# P_12_SOM_Interface.net
KiCad netlist of a schematic drawn in Altium Designer
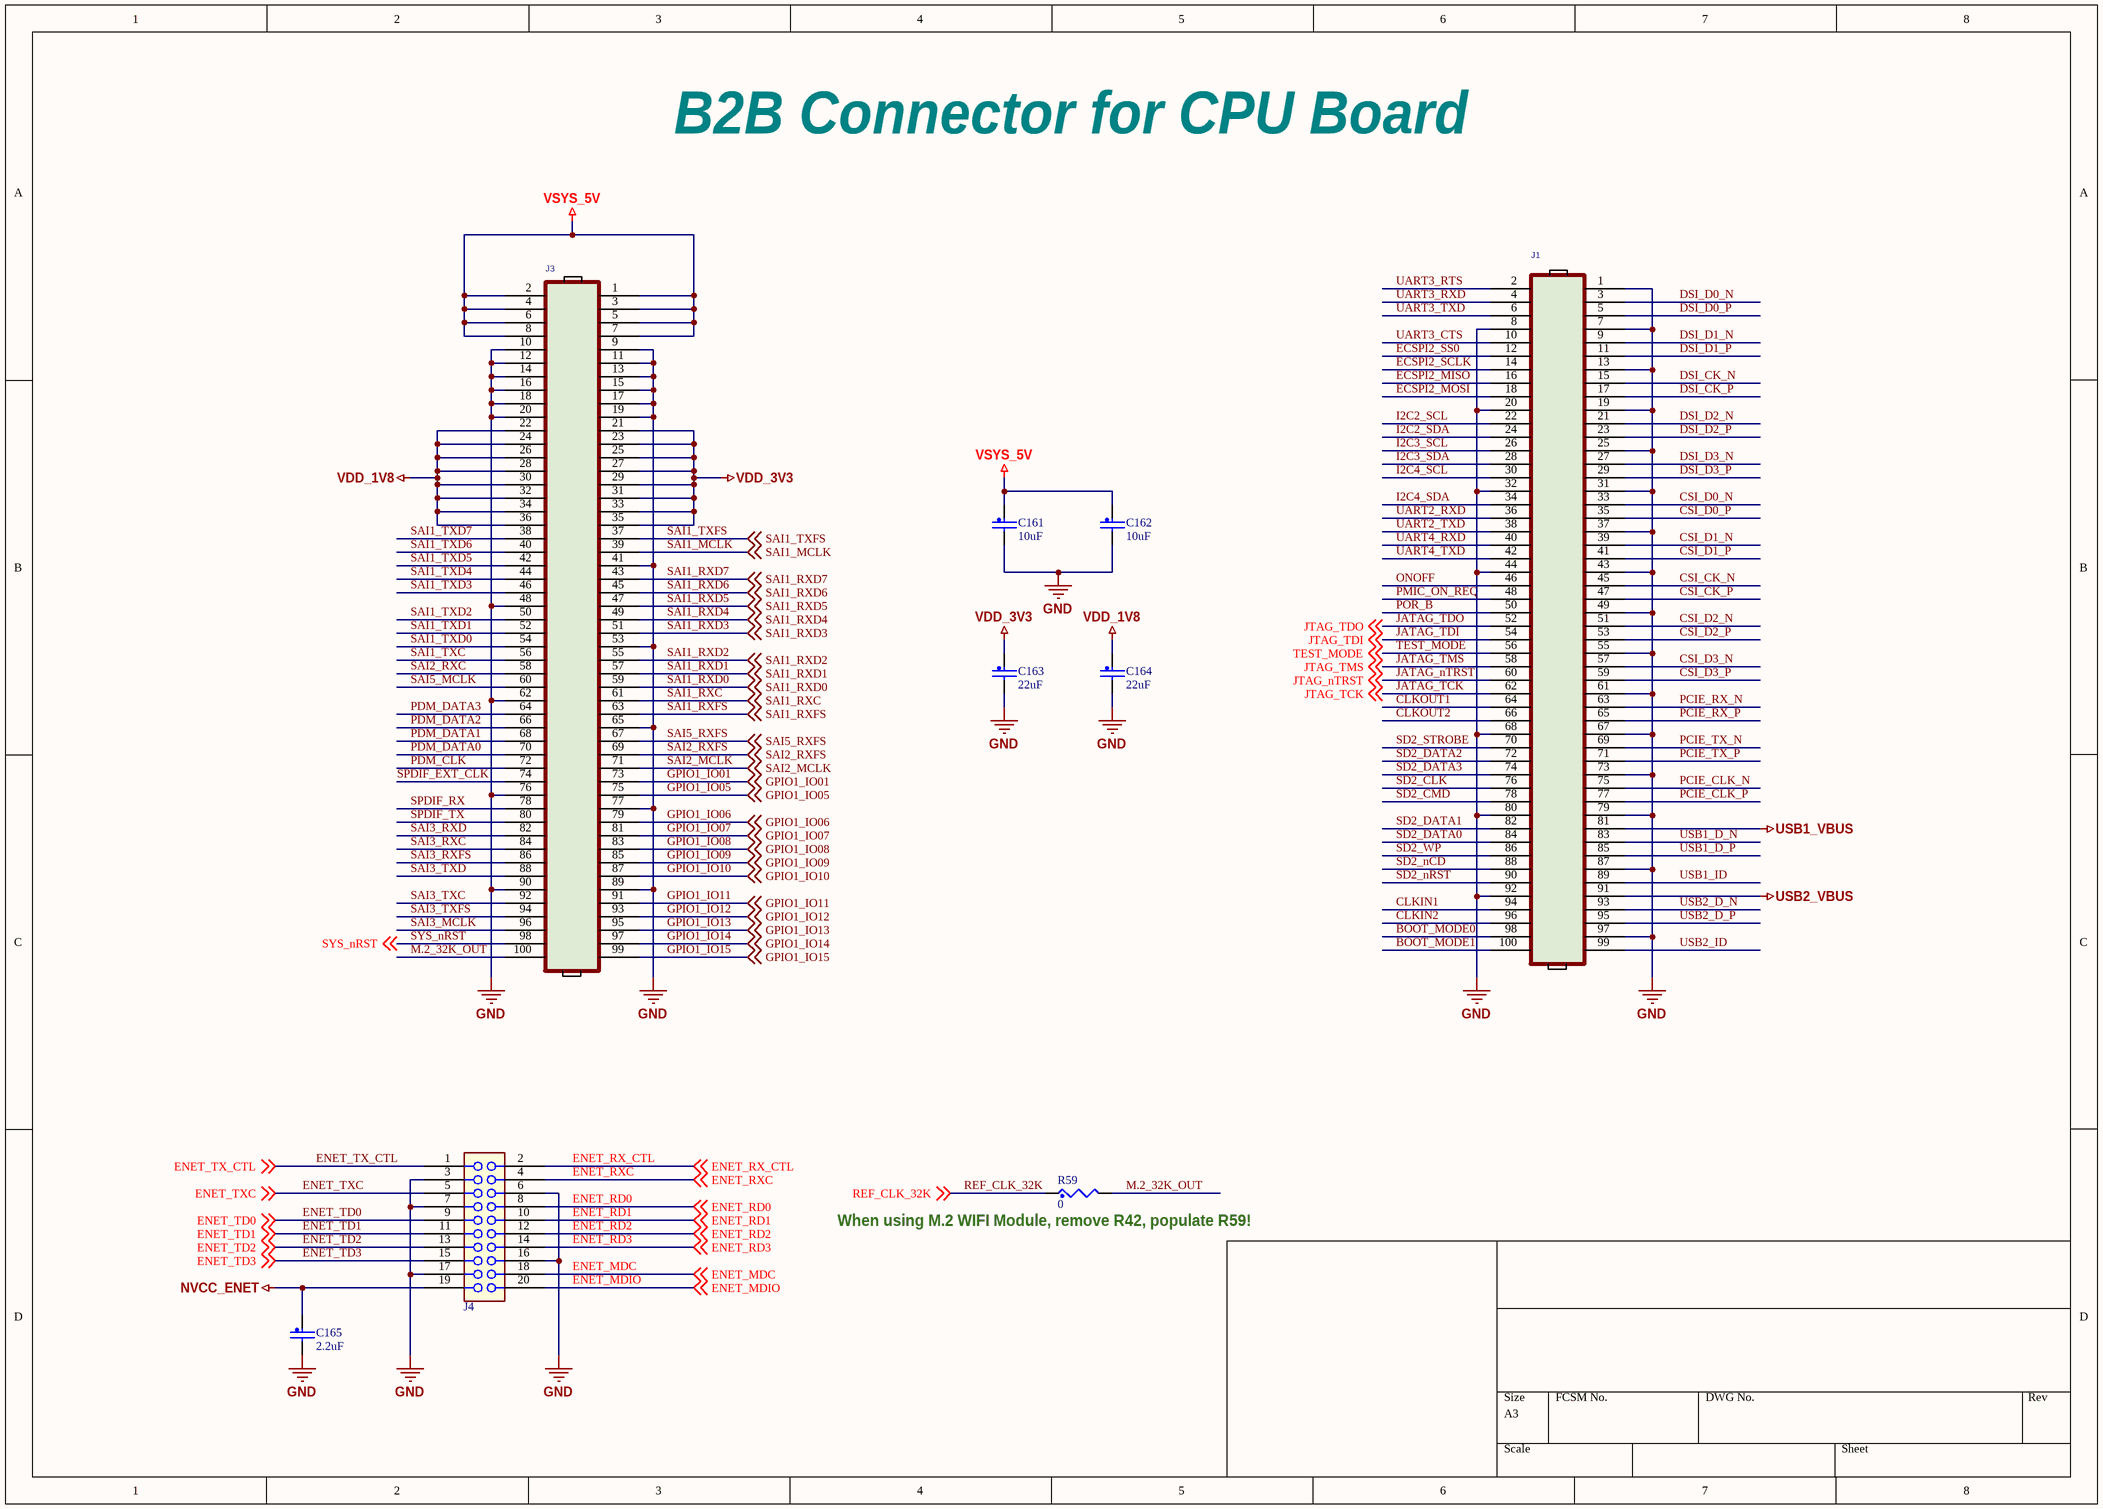
[diagram p0: P[12]SOM_Interface.SchDoc]

(export (version "E")
  (design (tool "Eeschema 10.0.6"))
  (components
    (comp (ref "C161") (value "10uF") (footprint "0603_CC") (libsource (lib "AA_iMX8_M_") (part "CAP_NP")))
    (comp (ref "C162") (value "10uF") (footprint "0603_CC") (libsource (lib "AA_iMX8_M_") (part "CAP_NP")))
    (comp (ref "C163") (value "22uF") (footprint "0603_CC") (libsource (lib "AA_iMX8_M_") (part "CAP_NP")))
    (comp (ref "C164") (value "22uF") (footprint "0603_CC") (libsource (lib "AA_iMX8_M_") (part "CAP_NP")))
    (comp (ref "C165")
      (value "2.2uF")
      (footprint "0402_CC - C")
      (libsource (lib "AA_iMX8_M_") (part "CAP_NP"))
    )
    (comp (ref "J1")
      (value "CON 2X50 PLUG SHRD SMT 0.4MM SP 51H AU")
      (footprint "CON100_0P4_21P7X2P05_SM")
      (libsource (lib "AA_iMX8_M_") (part "HDR_2X50_M"))
    )
    (comp (ref "J3")
      (value "CON 2X50 PLUG SHRD SMT 0.4MM SP 51H AU")
      (footprint "CON100_0P4_22P8X3P1_SM")
      (libsource (lib "AA_iMX8_M_") (part "HDR_2X50_M"))
    )
    (comp (ref "J4")
      (value "CONN_HDR_10X2_CON20_0P4_6P8X3P1")
      (footprint "CON20_0P4_6P8X3P1_SM")
      (description "CONN_HDR_10X2_CON20_0P4_6P8X3P1\\By Arman Arvand")
      (libsource (lib "AA_iMX8_M_") (part "CONN_HDR_10X2"))
    )
    (comp (ref "R59") (value "0") (footprint "0402_CC") (libsource (lib "AA_iMX8_M_") (part "RES")))
  )
  (nets
    (net (code "1") (name "/BOOT_MODE0") (class "Default")
      (node (ref "J1") (pin "98") (pinfunction "98_98") (pintype "passive"))
    )
    (net (code "2") (name "/BOOT_MODE1") (class "Default")
      (node (ref "J1") (pin "100") (pinfunction "100_100") (pintype "passive"))
    )
    (net (code "3") (name "/CLKIN1") (class "Default")
      (node (ref "J1") (pin "94") (pinfunction "94_94") (pintype "passive"))
    )
    (net (code "4") (name "/CLKIN2") (class "Default")
      (node (ref "J1") (pin "96") (pinfunction "96_96") (pintype "passive"))
    )
    (net (code "5") (name "/CLKOUT1") (class "Default")
      (node (ref "J1") (pin "64") (pinfunction "64_64") (pintype "passive"))
    )
    (net (code "6") (name "/CLKOUT2") (class "Default")
      (node (ref "J1") (pin "66") (pinfunction "66_66") (pintype "passive"))
    )
    (net (code "7") (name "/CSI_CK_N") (class "Default")
      (node (ref "J1") (pin "45") (pinfunction "45_45") (pintype "passive"))
    )
    (net (code "8") (name "/CSI_CK_P") (class "Default")
      (node (ref "J1") (pin "47") (pinfunction "47_47") (pintype "passive"))
    )
    (net (code "9") (name "/CSI_D0_N") (class "Default")
      (node (ref "J1") (pin "33") (pinfunction "33_33") (pintype "passive"))
    )
    (net (code "10") (name "/CSI_D0_P") (class "Default")
      (node (ref "J1") (pin "35") (pinfunction "35_35") (pintype "passive"))
    )
    (net (code "11") (name "/CSI_D1_N") (class "Default")
      (node (ref "J1") (pin "39") (pinfunction "39_39") (pintype "passive"))
    )
    (net (code "12") (name "/CSI_D1_P") (class "Default")
      (node (ref "J1") (pin "41") (pinfunction "41_41") (pintype "passive"))
    )
    (net (code "13") (name "/CSI_D2_N") (class "Default")
      (node (ref "J1") (pin "51") (pinfunction "51_51") (pintype "passive"))
    )
    (net (code "14") (name "/CSI_D2_P") (class "Default")
      (node (ref "J1") (pin "53") (pinfunction "53_53") (pintype "passive"))
    )
    (net (code "15") (name "/CSI_D3_N") (class "Default")
      (node (ref "J1") (pin "57") (pinfunction "57_57") (pintype "passive"))
    )
    (net (code "16") (name "/CSI_D3_P") (class "Default")
      (node (ref "J1") (pin "59") (pinfunction "59_59") (pintype "passive"))
    )
    (net (code "17") (name "/DSI_CK_N") (class "Default")
      (node (ref "J1") (pin "15") (pinfunction "15_15") (pintype "passive"))
    )
    (net (code "18") (name "/DSI_CK_P") (class "Default")
      (node (ref "J1") (pin "17") (pinfunction "17_17") (pintype "passive"))
    )
    (net (code "19") (name "/DSI_D0_N") (class "Default")
      (node (ref "J1") (pin "3") (pinfunction "3_3") (pintype "passive"))
    )
    (net (code "20") (name "/DSI_D0_P") (class "Default")
      (node (ref "J1") (pin "5") (pinfunction "5_5") (pintype "passive"))
    )
    (net (code "21") (name "/DSI_D1_N") (class "Default")
      (node (ref "J1") (pin "9") (pinfunction "9_9") (pintype "passive"))
    )
    (net (code "22") (name "/DSI_D1_P") (class "Default")
      (node (ref "J1") (pin "11") (pinfunction "11_11") (pintype "passive"))
    )
    (net (code "23") (name "/DSI_D2_N") (class "Default")
      (node (ref "J1") (pin "21") (pinfunction "21_21") (pintype "passive"))
    )
    (net (code "24") (name "/DSI_D2_P") (class "Default")
      (node (ref "J1") (pin "23") (pinfunction "23_23") (pintype "passive"))
    )
    (net (code "25") (name "/DSI_D3_N") (class "Default")
      (node (ref "J1") (pin "27") (pinfunction "27_27") (pintype "passive"))
    )
    (net (code "26") (name "/DSI_D3_P") (class "Default")
      (node (ref "J1") (pin "29") (pinfunction "29_29") (pintype "passive"))
    )
    (net (code "27") (name "/ECSPI2_MISO") (class "Default")
      (node (ref "J1") (pin "16") (pinfunction "16_16") (pintype "passive"))
    )
    (net (code "28") (name "/ECSPI2_MOSI") (class "Default")
      (node (ref "J1") (pin "18") (pinfunction "18_18") (pintype "passive"))
    )
    (net (code "29") (name "/ECSPI2_SCLK") (class "Default")
      (node (ref "J1") (pin "14") (pinfunction "14_14") (pintype "passive"))
    )
    (net (code "30") (name "/ECSPI2_SS0") (class "Default")
      (node (ref "J1") (pin "12") (pinfunction "12_12") (pintype "passive"))
    )
    (net (code "31") (name "/I2C2_SCL") (class "Default")
      (node (ref "J1") (pin "22") (pinfunction "22_22") (pintype "passive"))
    )
    (net (code "32") (name "/I2C2_SDA") (class "Default")
      (node (ref "J1") (pin "24") (pinfunction "24_24") (pintype "passive"))
    )
    (net (code "33") (name "/I2C3_SCL") (class "Default")
      (node (ref "J1") (pin "26") (pinfunction "26_26") (pintype "passive"))
    )
    (net (code "34") (name "/I2C3_SDA") (class "Default")
      (node (ref "J1") (pin "28") (pinfunction "28_28") (pintype "passive"))
    )
    (net (code "35") (name "/I2C4_SCL") (class "Default")
      (node (ref "J1") (pin "30") (pinfunction "30_30") (pintype "passive"))
    )
    (net (code "36") (name "/I2C4_SDA") (class "Default")
      (node (ref "J1") (pin "34") (pinfunction "34_34") (pintype "passive"))
    )
    (net (code "37") (name "/M.2_32K_OUT") (class "Default")
      (node (ref "J3") (pin "100") (pinfunction "100_100") (pintype "passive"))
      (node (ref "R59") (pin "2") (pinfunction "2_2") (pintype "passive"))
    )
    (net (code "38") (name "/ONOFF") (class "Default")
      (node (ref "J1") (pin "46") (pinfunction "46_46") (pintype "passive"))
    )
    (net (code "39") (name "/PCIE_CLK_N") (class "Default")
      (node (ref "J1") (pin "75") (pinfunction "75_75") (pintype "passive"))
    )
    (net (code "40") (name "/PCIE_CLK_P") (class "Default")
      (node (ref "J1") (pin "77") (pinfunction "77_77") (pintype "passive"))
    )
    (net (code "41") (name "/PCIE_RX_N") (class "Default")
      (node (ref "J1") (pin "63") (pinfunction "63_63") (pintype "passive"))
    )
    (net (code "42") (name "/PCIE_RX_P") (class "Default")
      (node (ref "J1") (pin "65") (pinfunction "65_65") (pintype "passive"))
    )
    (net (code "43") (name "/PCIE_TX_N") (class "Default")
      (node (ref "J1") (pin "69") (pinfunction "69_69") (pintype "passive"))
    )
    (net (code "44") (name "/PCIE_TX_P") (class "Default")
      (node (ref "J1") (pin "71") (pinfunction "71_71") (pintype "passive"))
    )
    (net (code "45") (name "/PDM_CLK") (class "Default")
      (node (ref "J3") (pin "72") (pinfunction "72_72") (pintype "passive"))
    )
    (net (code "46") (name "/PDM_DATA0") (class "Default")
      (node (ref "J3") (pin "70") (pinfunction "70_70") (pintype "passive"))
    )
    (net (code "47") (name "/PDM_DATA1") (class "Default")
      (node (ref "J3") (pin "68") (pinfunction "68_68") (pintype "passive"))
    )
    (net (code "48") (name "/PDM_DATA2") (class "Default")
      (node (ref "J3") (pin "66") (pinfunction "66_66") (pintype "passive"))
    )
    (net (code "49") (name "/PDM_DATA3") (class "Default")
      (node (ref "J3") (pin "64") (pinfunction "64_64") (pintype "passive"))
    )
    (net (code "50") (name "/PMIC_ON_REQ") (class "Default")
      (node (ref "J1") (pin "48") (pinfunction "48_48") (pintype "passive"))
    )
    (net (code "51") (name "/POR_B") (class "Default")
      (node (ref "J1") (pin "50") (pinfunction "50_50") (pintype "passive"))
    )
    (net (code "52") (name "/SAI1_TXC") (class "Default")
      (node (ref "J3") (pin "56") (pinfunction "56_56") (pintype "passive"))
    )
    (net (code "53") (name "/SAI1_TXD0") (class "Default")
      (node (ref "J3") (pin "54") (pinfunction "54_54") (pintype "passive"))
    )
    (net (code "54") (name "/SAI1_TXD1") (class "Default")
      (node (ref "J3") (pin "52") (pinfunction "52_52") (pintype "passive"))
    )
    (net (code "55") (name "/SAI1_TXD2") (class "Default")
      (node (ref "J3") (pin "50") (pinfunction "50_50") (pintype "passive"))
    )
    (net (code "56") (name "/SAI1_TXD3") (class "Default")
      (node (ref "J3") (pin "46") (pinfunction "46_46") (pintype "passive"))
    )
    (net (code "57") (name "/SAI1_TXD4") (class "Default")
      (node (ref "J3") (pin "44") (pinfunction "44_44") (pintype "passive"))
    )
    (net (code "58") (name "/SAI1_TXD5") (class "Default")
      (node (ref "J3") (pin "42") (pinfunction "42_42") (pintype "passive"))
    )
    (net (code "59") (name "/SAI1_TXD6") (class "Default")
      (node (ref "J3") (pin "40") (pinfunction "40_40") (pintype "passive"))
    )
    (net (code "60") (name "/SAI1_TXD7") (class "Default")
      (node (ref "J3") (pin "38") (pinfunction "38_38") (pintype "passive"))
    )
    (net (code "61") (name "/SAI2_RXC") (class "Default")
      (node (ref "J3") (pin "58") (pinfunction "58_58") (pintype "passive"))
    )
    (net (code "62") (name "/SAI3_MCLK") (class "Default")
      (node (ref "J3") (pin "96") (pinfunction "96_96") (pintype "passive"))
    )
    (net (code "63") (name "/SAI3_RXC") (class "Default")
      (node (ref "J3") (pin "84") (pinfunction "84_84") (pintype "passive"))
    )
    (net (code "64") (name "/SAI3_RXD") (class "Default")
      (node (ref "J3") (pin "82") (pinfunction "82_82") (pintype "passive"))
    )
    (net (code "65") (name "/SAI3_RXFS") (class "Default")
      (node (ref "J3") (pin "86") (pinfunction "86_86") (pintype "passive"))
    )
    (net (code "66") (name "/SAI3_TXC") (class "Default")
      (node (ref "J3") (pin "92") (pinfunction "92_92") (pintype "passive"))
    )
    (net (code "67") (name "/SAI3_TXD") (class "Default")
      (node (ref "J3") (pin "88") (pinfunction "88_88") (pintype "passive"))
    )
    (net (code "68") (name "/SAI3_TXFS") (class "Default")
      (node (ref "J3") (pin "94") (pinfunction "94_94") (pintype "passive"))
    )
    (net (code "69") (name "/SAI5_MCLK") (class "Default")
      (node (ref "J3") (pin "60") (pinfunction "60_60") (pintype "passive"))
    )
    (net (code "70") (name "/SD2_CLK") (class "Default")
      (node (ref "J1") (pin "76") (pinfunction "76_76") (pintype "passive"))
    )
    (net (code "71") (name "/SD2_CMD") (class "Default")
      (node (ref "J1") (pin "78") (pinfunction "78_78") (pintype "passive"))
    )
    (net (code "72") (name "/SD2_DATA0") (class "Default")
      (node (ref "J1") (pin "84") (pinfunction "84_84") (pintype "passive"))
    )
    (net (code "73") (name "/SD2_DATA1") (class "Default")
      (node (ref "J1") (pin "82") (pinfunction "82_82") (pintype "passive"))
    )
    (net (code "74") (name "/SD2_DATA2") (class "Default")
      (node (ref "J1") (pin "72") (pinfunction "72_72") (pintype "passive"))
    )
    (net (code "75") (name "/SD2_DATA3") (class "Default")
      (node (ref "J1") (pin "74") (pinfunction "74_74") (pintype "passive"))
    )
    (net (code "76") (name "/SD2_STROBE") (class "Default")
      (node (ref "J1") (pin "70") (pinfunction "70_70") (pintype "passive"))
    )
    (net (code "77") (name "/SD2_WP") (class "Default")
      (node (ref "J1") (pin "86") (pinfunction "86_86") (pintype "passive"))
    )
    (net (code "78") (name "/SD2_nCD") (class "Default")
      (node (ref "J1") (pin "88") (pinfunction "88_88") (pintype "passive"))
    )
    (net (code "79") (name "/SD2_nRST") (class "Default")
      (node (ref "J1") (pin "90") (pinfunction "90_90") (pintype "passive"))
    )
    (net (code "80") (name "/SPDIF_EXT_CLK") (class "Default")
      (node (ref "J3") (pin "74") (pinfunction "74_74") (pintype "passive"))
    )
    (net (code "81") (name "/SPDIF_RX") (class "Default")
      (node (ref "J3") (pin "78") (pinfunction "78_78") (pintype "passive"))
    )
    (net (code "82") (name "/SPDIF_TX") (class "Default")
      (node (ref "J3") (pin "80") (pinfunction "80_80") (pintype "passive"))
    )
    (net (code "83") (name "/UART2_RXD") (class "Default")
      (node (ref "J1") (pin "36") (pinfunction "36_36") (pintype "passive"))
    )
    (net (code "84") (name "/UART2_TXD") (class "Default")
      (node (ref "J1") (pin "38") (pinfunction "38_38") (pintype "passive"))
    )
    (net (code "85") (name "/UART3_CTS") (class "Default")
      (node (ref "J1") (pin "10") (pinfunction "10_10") (pintype "passive"))
    )
    (net (code "86") (name "/UART3_RTS") (class "Default")
      (node (ref "J1") (pin "2") (pinfunction "2_2") (pintype "passive"))
    )
    (net (code "87") (name "/UART3_RXD") (class "Default")
      (node (ref "J1") (pin "4") (pinfunction "4_4") (pintype "passive"))
    )
    (net (code "88") (name "/UART3_TXD") (class "Default")
      (node (ref "J1") (pin "6") (pinfunction "6_6") (pintype "passive"))
    )
    (net (code "89") (name "/UART4_RXD") (class "Default")
      (node (ref "J1") (pin "40") (pinfunction "40_40") (pintype "passive"))
    )
    (net (code "90") (name "/UART4_TXD") (class "Default")
      (node (ref "J1") (pin "42") (pinfunction "42_42") (pintype "passive"))
    )
    (net (code "91") (name "/USB1_D_N") (class "Default")
      (node (ref "J1") (pin "83") (pinfunction "83_83") (pintype "passive"))
    )
    (net (code "92") (name "/USB1_D_P") (class "Default")
      (node (ref "J1") (pin "85") (pinfunction "85_85") (pintype "passive"))
    )
    (net (code "93") (name "/USB1_ID") (class "Default")
      (node (ref "J1") (pin "89") (pinfunction "89_89") (pintype "passive"))
    )
    (net (code "94") (name "/USB2_D_N") (class "Default")
      (node (ref "J1") (pin "93") (pinfunction "93_93") (pintype "passive"))
    )
    (net (code "95") (name "/USB2_D_P") (class "Default")
      (node (ref "J1") (pin "95") (pinfunction "95_95") (pintype "passive"))
    )
    (net (code "96") (name "/USB2_ID") (class "Default")
      (node (ref "J1") (pin "99") (pinfunction "99_99") (pintype "passive"))
    )
    (net (code "97") (name "ENET_MDC") (class "Default")
      (node (ref "J4") (pin "18") (pinfunction "18_18") (pintype "passive"))
    )
    (net (code "98") (name "ENET_MDIO") (class "Default")
      (node (ref "J4") (pin "20") (pinfunction "20_20") (pintype "passive"))
    )
    (net (code "99") (name "ENET_RD0") (class "Default")
      (node (ref "J4") (pin "8") (pinfunction "8_8") (pintype "passive"))
    )
    (net (code "100") (name "ENET_RD1") (class "Default")
      (node (ref "J4") (pin "10") (pinfunction "10_10") (pintype "passive"))
    )
    (net (code "101") (name "ENET_RD2") (class "Default")
      (node (ref "J4") (pin "12") (pinfunction "12_12") (pintype "passive"))
    )
    (net (code "102") (name "ENET_RD3") (class "Default")
      (node (ref "J4") (pin "14") (pinfunction "14_14") (pintype "passive"))
    )
    (net (code "103") (name "ENET_RXC") (class "Default")
      (node (ref "J4") (pin "4") (pinfunction "4_4") (pintype "passive"))
    )
    (net (code "104") (name "ENET_RX_CTL") (class "Default")
      (node (ref "J4") (pin "2") (pinfunction "2_2") (pintype "passive"))
    )
    (net (code "105") (name "ENET_TD0") (class "Default")
      (node (ref "J4") (pin "9") (pinfunction "9_9") (pintype "passive"))
    )
    (net (code "106") (name "ENET_TD1") (class "Default")
      (node (ref "J4") (pin "11") (pinfunction "11_11") (pintype "passive"))
    )
    (net (code "107") (name "ENET_TD2") (class "Default")
      (node (ref "J4") (pin "13") (pinfunction "13_13") (pintype "passive"))
    )
    (net (code "108") (name "ENET_TD3") (class "Default")
      (node (ref "J4") (pin "15") (pinfunction "15_15") (pintype "passive"))
    )
    (net (code "109") (name "ENET_TXC") (class "Default")
      (node (ref "J4") (pin "5") (pinfunction "5_5") (pintype "passive"))
    )
    (net (code "110") (name "ENET_TX_CTL") (class "Default")
      (node (ref "J4") (pin "1") (pinfunction "1_1") (pintype "passive"))
    )
    (net (code "111") (name "GND") (class "Default")
      (node (ref "C161") (pin "2") (pinfunction "2_2") (pintype "passive"))
      (node (ref "C162") (pin "2") (pinfunction "2_2") (pintype "passive"))
      (node (ref "C163") (pin "2") (pinfunction "2_2") (pintype "passive"))
      (node (ref "C164") (pin "2") (pinfunction "2_2") (pintype "passive"))
      (node (ref "C165") (pin "2") (pinfunction "2_2") (pintype "passive"))
      (node (ref "J1") (pin "1") (pinfunction "1_1") (pintype "passive"))
      (node (ref "J1") (pin "13") (pinfunction "13_13") (pintype "passive"))
      (node (ref "J1") (pin "19") (pinfunction "19_19") (pintype "passive"))
      (node (ref "J1") (pin "20") (pinfunction "20_20") (pintype "passive"))
      (node (ref "J1") (pin "25") (pinfunction "25_25") (pintype "passive"))
      (node (ref "J1") (pin "31") (pinfunction "31_31") (pintype "passive"))
      (node (ref "J1") (pin "32") (pinfunction "32_32") (pintype "passive"))
      (node (ref "J1") (pin "37") (pinfunction "37_37") (pintype "passive"))
      (node (ref "J1") (pin "43") (pinfunction "43_43") (pintype "passive"))
      (node (ref "J1") (pin "44") (pinfunction "44_44") (pintype "passive"))
      (node (ref "J1") (pin "49") (pinfunction "49_49") (pintype "passive"))
      (node (ref "J1") (pin "55") (pinfunction "55_55") (pintype "passive"))
      (node (ref "J1") (pin "61") (pinfunction "61_61") (pintype "passive"))
      (node (ref "J1") (pin "67") (pinfunction "67_67") (pintype "passive"))
      (node (ref "J1") (pin "68") (pinfunction "68_68") (pintype "passive"))
      (node (ref "J1") (pin "7") (pinfunction "7_7") (pintype "passive"))
      (node (ref "J1") (pin "73") (pinfunction "73_73") (pintype "passive"))
      (node (ref "J1") (pin "79") (pinfunction "79_79") (pintype "passive"))
      (node (ref "J1") (pin "8") (pinfunction "8_8") (pintype "passive"))
      (node (ref "J1") (pin "80") (pinfunction "80_80") (pintype "passive"))
      (node (ref "J1") (pin "87") (pinfunction "87_87") (pintype "passive"))
      (node (ref "J1") (pin "92") (pinfunction "92_92") (pintype "passive"))
      (node (ref "J1") (pin "97") (pinfunction "97_97") (pintype "passive"))
      (node (ref "J3") (pin "10") (pinfunction "10_10") (pintype "passive"))
      (node (ref "J3") (pin "11") (pinfunction "11_11") (pintype "passive"))
      (node (ref "J3") (pin "12") (pinfunction "12_12") (pintype "passive"))
      (node (ref "J3") (pin "13") (pinfunction "13_13") (pintype "passive"))
      (node (ref "J3") (pin "14") (pinfunction "14_14") (pintype "passive"))
      (node (ref "J3") (pin "15") (pinfunction "15_15") (pintype "passive"))
      (node (ref "J3") (pin "16") (pinfunction "16_16") (pintype "passive"))
      (node (ref "J3") (pin "17") (pinfunction "17_17") (pintype "passive"))
      (node (ref "J3") (pin "18") (pinfunction "18_18") (pintype "passive"))
      (node (ref "J3") (pin "19") (pinfunction "19_19") (pintype "passive"))
      (node (ref "J3") (pin "20") (pinfunction "20_20") (pintype "passive"))
      (node (ref "J3") (pin "41") (pinfunction "41_41") (pintype "passive"))
      (node (ref "J3") (pin "48") (pinfunction "48_48") (pintype "passive"))
      (node (ref "J3") (pin "53") (pinfunction "53_53") (pintype "passive"))
      (node (ref "J3") (pin "62") (pinfunction "62_62") (pintype "passive"))
      (node (ref "J3") (pin "65") (pinfunction "65_65") (pintype "passive"))
      (node (ref "J3") (pin "76") (pinfunction "76_76") (pintype "passive"))
      (node (ref "J3") (pin "77") (pinfunction "77_77") (pintype "passive"))
      (node (ref "J3") (pin "89") (pinfunction "89_89") (pintype "passive"))
      (node (ref "J3") (pin "9") (pinfunction "9_9") (pintype "passive"))
      (node (ref "J3") (pin "90") (pinfunction "90_90") (pintype "passive"))
      (node (ref "J4") (pin "16") (pinfunction "16_16") (pintype "passive"))
      (node (ref "J4") (pin "17") (pinfunction "17_17") (pintype "passive"))
      (node (ref "J4") (pin "3") (pinfunction "3_3") (pintype "passive"))
      (node (ref "J4") (pin "6") (pinfunction "6_6") (pintype "passive"))
      (node (ref "J4") (pin "7") (pinfunction "7_7") (pintype "passive"))
    )
    (net (code "112") (name "GPIO1_IO01") (class "Default")
      (node (ref "J3") (pin "73") (pinfunction "73_73") (pintype "passive"))
    )
    (net (code "113") (name "GPIO1_IO05") (class "Default")
      (node (ref "J3") (pin "75") (pinfunction "75_75") (pintype "passive"))
    )
    (net (code "114") (name "GPIO1_IO06") (class "Default")
      (node (ref "J3") (pin "79") (pinfunction "79_79") (pintype "passive"))
    )
    (net (code "115") (name "GPIO1_IO07") (class "Default")
      (node (ref "J3") (pin "81") (pinfunction "81_81") (pintype "passive"))
    )
    (net (code "116") (name "GPIO1_IO08") (class "Default")
      (node (ref "J3") (pin "83") (pinfunction "83_83") (pintype "passive"))
    )
    (net (code "117") (name "GPIO1_IO09") (class "Default")
      (node (ref "J3") (pin "85") (pinfunction "85_85") (pintype "passive"))
    )
    (net (code "118") (name "GPIO1_IO10") (class "Default")
      (node (ref "J3") (pin "87") (pinfunction "87_87") (pintype "passive"))
    )
    (net (code "119") (name "GPIO1_IO11") (class "Default")
      (node (ref "J3") (pin "91") (pinfunction "91_91") (pintype "passive"))
    )
    (net (code "120") (name "GPIO1_IO12") (class "Default")
      (node (ref "J3") (pin "93") (pinfunction "93_93") (pintype "passive"))
    )
    (net (code "121") (name "GPIO1_IO13") (class "Default")
      (node (ref "J3") (pin "95") (pinfunction "95_95") (pintype "passive"))
    )
    (net (code "122") (name "GPIO1_IO14") (class "Default")
      (node (ref "J3") (pin "97") (pinfunction "97_97") (pintype "passive"))
    )
    (net (code "123") (name "GPIO1_IO15") (class "Default")
      (node (ref "J3") (pin "99") (pinfunction "99_99") (pintype "passive"))
    )
    (net (code "124") (name "JTAG_TCK") (class "Default")
      (node (ref "J1") (pin "62") (pinfunction "62_62") (pintype "passive"))
    )
    (net (code "125") (name "JTAG_TDI") (class "Default")
      (node (ref "J1") (pin "54") (pinfunction "54_54") (pintype "passive"))
    )
    (net (code "126") (name "JTAG_TDO") (class "Default")
      (node (ref "J1") (pin "52") (pinfunction "52_52") (pintype "passive"))
    )
    (net (code "127") (name "JTAG_TMS") (class "Default")
      (node (ref "J1") (pin "58") (pinfunction "58_58") (pintype "passive"))
    )
    (net (code "128") (name "JTAG_nTRST") (class "Default")
      (node (ref "J1") (pin "60") (pinfunction "60_60") (pintype "passive"))
    )
    (net (code "129") (name "NVCC_ENET") (class "Default")
      (node (ref "C165") (pin "1") (pinfunction "1_1") (pintype "passive"))
      (node (ref "J4") (pin "19") (pinfunction "19_19") (pintype "passive"))
    )
    (net (code "130") (name "REF_CLK_32K") (class "Default")
      (node (ref "R59") (pin "1") (pinfunction "1_1") (pintype "passive"))
    )
    (net (code "131") (name "SAI1_MCLK") (class "Default")
      (node (ref "J3") (pin "39") (pinfunction "39_39") (pintype "passive"))
    )
    (net (code "132") (name "SAI1_RXC") (class "Default")
      (node (ref "J3") (pin "61") (pinfunction "61_61") (pintype "passive"))
    )
    (net (code "133") (name "SAI1_RXD0") (class "Default")
      (node (ref "J3") (pin "59") (pinfunction "59_59") (pintype "passive"))
    )
    (net (code "134") (name "SAI1_RXD1") (class "Default")
      (node (ref "J3") (pin "57") (pinfunction "57_57") (pintype "passive"))
    )
    (net (code "135") (name "SAI1_RXD2") (class "Default")
      (node (ref "J3") (pin "55") (pinfunction "55_55") (pintype "passive"))
    )
    (net (code "136") (name "SAI1_RXD3") (class "Default")
      (node (ref "J3") (pin "51") (pinfunction "51_51") (pintype "passive"))
    )
    (net (code "137") (name "SAI1_RXD4") (class "Default")
      (node (ref "J3") (pin "49") (pinfunction "49_49") (pintype "passive"))
    )
    (net (code "138") (name "SAI1_RXD5") (class "Default")
      (node (ref "J3") (pin "47") (pinfunction "47_47") (pintype "passive"))
    )
    (net (code "139") (name "SAI1_RXD6") (class "Default")
      (node (ref "J3") (pin "45") (pinfunction "45_45") (pintype "passive"))
    )
    (net (code "140") (name "SAI1_RXD7") (class "Default")
      (node (ref "J3") (pin "43") (pinfunction "43_43") (pintype "passive"))
    )
    (net (code "141") (name "SAI1_RXFS") (class "Default")
      (node (ref "J3") (pin "63") (pinfunction "63_63") (pintype "passive"))
    )
    (net (code "142") (name "SAI1_TXFS") (class "Default")
      (node (ref "J3") (pin "37") (pinfunction "37_37") (pintype "passive"))
    )
    (net (code "143") (name "SAI2_MCLK") (class "Default")
      (node (ref "J3") (pin "71") (pinfunction "71_71") (pintype "passive"))
    )
    (net (code "144") (name "SAI2_RXFS") (class "Default")
      (node (ref "J3") (pin "69") (pinfunction "69_69") (pintype "passive"))
    )
    (net (code "145") (name "SAI5_RXFS") (class "Default")
      (node (ref "J3") (pin "67") (pinfunction "67_67") (pintype "passive"))
    )
    (net (code "146") (name "SYS_nRST") (class "Default")
      (node (ref "J3") (pin "98") (pinfunction "98_98") (pintype "passive"))
    )
    (net (code "147") (name "TEST_MODE") (class "Default")
      (node (ref "J1") (pin "56") (pinfunction "56_56") (pintype "passive"))
    )
    (net (code "148") (name "USB1_VBUS") (class "Default")
      (node (ref "J1") (pin "81") (pinfunction "81_81") (pintype "passive"))
    )
    (net (code "149") (name "USB2_VBUS") (class "Default")
      (node (ref "J1") (pin "91") (pinfunction "91_91") (pintype "passive"))
    )
    (net (code "150") (name "VDD_1V8") (class "Default")
      (node (ref "C164") (pin "1") (pinfunction "1_1") (pintype "passive"))
      (node (ref "J3") (pin "22") (pinfunction "22_22") (pintype "passive"))
      (node (ref "J3") (pin "24") (pinfunction "24_24") (pintype "passive"))
      (node (ref "J3") (pin "26") (pinfunction "26_26") (pintype "passive"))
      (node (ref "J3") (pin "28") (pinfunction "28_28") (pintype "passive"))
      (node (ref "J3") (pin "30") (pinfunction "30_30") (pintype "passive"))
      (node (ref "J3") (pin "32") (pinfunction "32_32") (pintype "passive"))
      (node (ref "J3") (pin "34") (pinfunction "34_34") (pintype "passive"))
      (node (ref "J3") (pin "36") (pinfunction "36_36") (pintype "passive"))
    )
    (net (code "151") (name "VDD_3V3") (class "Default")
      (node (ref "C163") (pin "1") (pinfunction "1_1") (pintype "passive"))
      (node (ref "J3") (pin "21") (pinfunction "21_21") (pintype "passive"))
      (node (ref "J3") (pin "23") (pinfunction "23_23") (pintype "passive"))
      (node (ref "J3") (pin "25") (pinfunction "25_25") (pintype "passive"))
      (node (ref "J3") (pin "27") (pinfunction "27_27") (pintype "passive"))
      (node (ref "J3") (pin "29") (pinfunction "29_29") (pintype "passive"))
      (node (ref "J3") (pin "31") (pinfunction "31_31") (pintype "passive"))
      (node (ref "J3") (pin "33") (pinfunction "33_33") (pintype "passive"))
      (node (ref "J3") (pin "35") (pinfunction "35_35") (pintype "passive"))
    )
    (net (code "152") (name "VSYS_5V") (class "Default")
      (node (ref "C161") (pin "1") (pinfunction "1_1") (pintype "passive"))
      (node (ref "C162") (pin "1") (pinfunction "1_1") (pintype "passive"))
      (node (ref "J3") (pin "1") (pinfunction "1_1") (pintype "passive"))
      (node (ref "J3") (pin "2") (pinfunction "2_2") (pintype "passive"))
      (node (ref "J3") (pin "3") (pinfunction "3_3") (pintype "passive"))
      (node (ref "J3") (pin "4") (pinfunction "4_4") (pintype "passive"))
      (node (ref "J3") (pin "5") (pinfunction "5_5") (pintype "passive"))
      (node (ref "J3") (pin "6") (pinfunction "6_6") (pintype "passive"))
      (node (ref "J3") (pin "7") (pinfunction "7_7") (pintype "passive"))
      (node (ref "J3") (pin "8") (pinfunction "8_8") (pintype "passive"))
    )
  )
)
